# SNAC_7ch_SNES_in_Housing_-_Minimal_with_.net
KiCad netlist of a schematic drawn in EAGLE
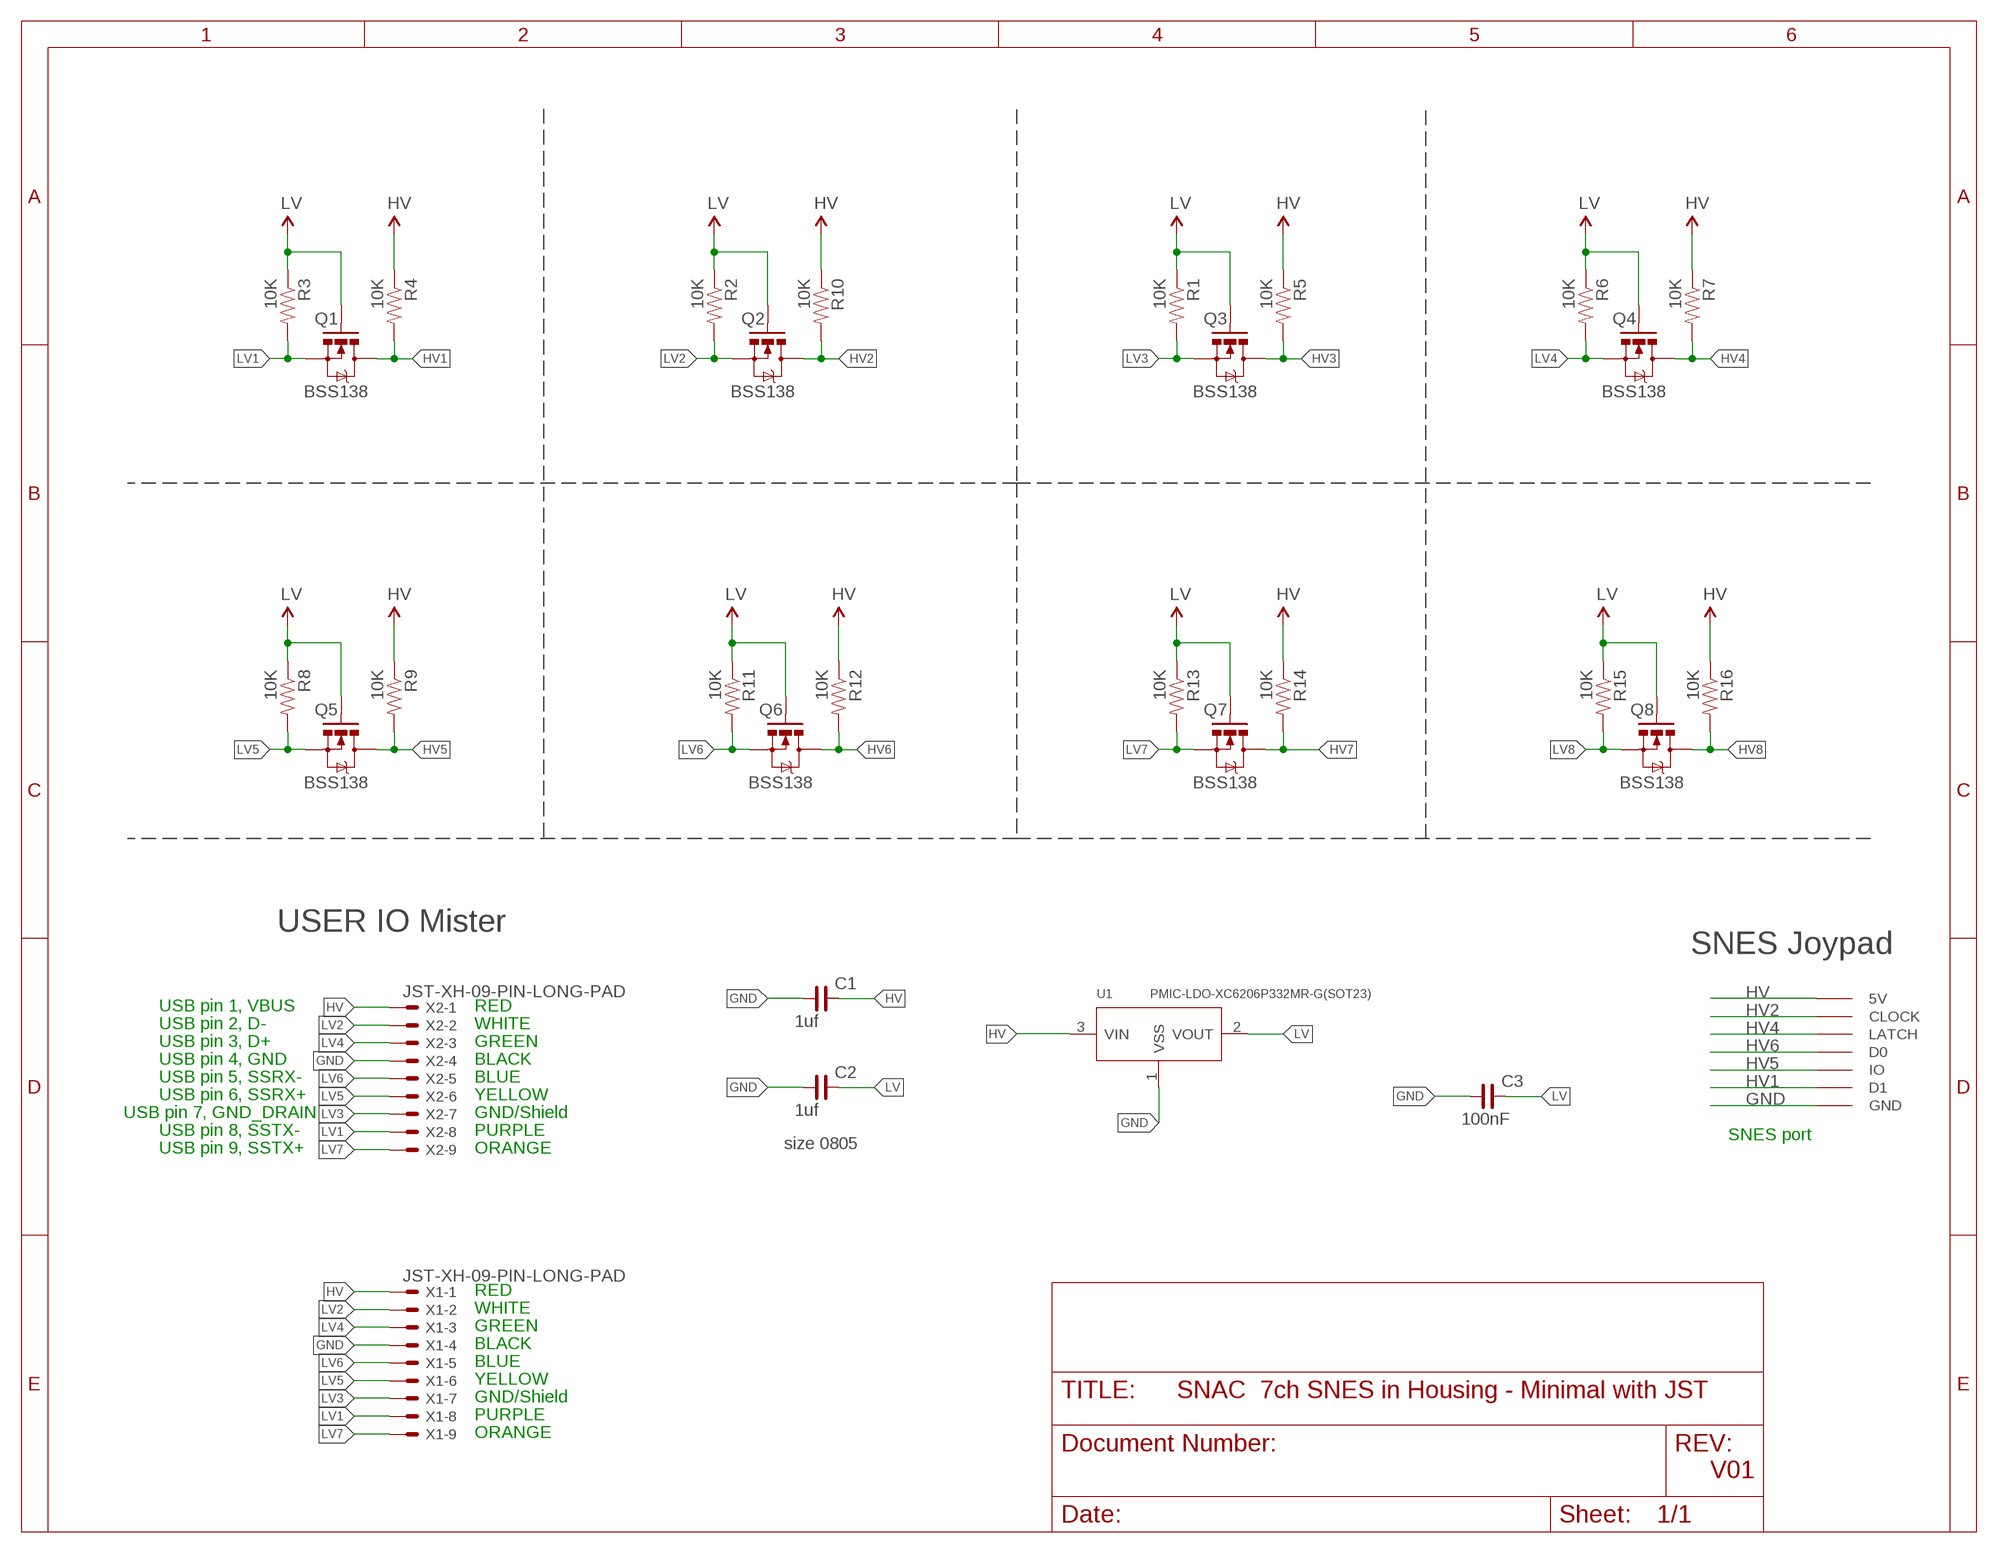
[diagram p0: schematic, sheet 1]

(export (version "E")
  (design (tool "Eeschema 10.0.6"))
  (components
    (comp (ref "C1")
      (value "1uf")
      (footprint "eagle-import:C0805")
      (libsource (lib "eagle-import") (part "C_0805"))
    )
    (comp (ref "C2")
      (value "1uf")
      (footprint "eagle-import:C0805")
      (libsource (lib "eagle-import") (part "C_0805"))
    )
    (comp (ref "C3")
      (value "100nF")
      (footprint "eagle-import:C0805")
      (libsource (lib "eagle-import") (part "C_0805"))
    )
    (comp (ref "Q1")
      (value "BSS138")
      (footprint "eagle-import:SOT23-3")
      (libsource (lib "eagle-import") (part "MOSFET-NCHANNELSMD"))
    )
    (comp (ref "Q2")
      (value "BSS138")
      (footprint "eagle-import:SOT23-3")
      (libsource (lib "eagle-import") (part "MOSFET-NCHANNELSMD"))
    )
    (comp (ref "Q3")
      (value "BSS138")
      (footprint "eagle-import:SOT23-3")
      (libsource (lib "eagle-import") (part "MOSFET-NCHANNELSMD"))
    )
    (comp (ref "Q4")
      (value "BSS138")
      (footprint "eagle-import:SOT23-3")
      (libsource (lib "eagle-import") (part "MOSFET-NCHANNELSMD"))
    )
    (comp (ref "Q5")
      (value "BSS138")
      (footprint "eagle-import:SOT23-3")
      (libsource (lib "eagle-import") (part "MOSFET-NCHANNELSMD"))
    )
    (comp (ref "Q6")
      (value "BSS138")
      (footprint "eagle-import:SOT23-3")
      (libsource (lib "eagle-import") (part "MOSFET-NCHANNELSMD"))
    )
    (comp (ref "Q7")
      (value "BSS138")
      (footprint "eagle-import:SOT23-3")
      (libsource (lib "eagle-import") (part "MOSFET-NCHANNELSMD"))
    )
    (comp (ref "Q8")
      (value "BSS138")
      (footprint "eagle-import:SOT23-3")
      (libsource (lib "eagle-import") (part "MOSFET-NCHANNELSMD"))
    )
    (comp (ref "R1")
      (value "10K")
      (footprint "eagle-import:0603-RES")
      (libsource (lib "eagle-import") (part "RESISTOR0603-RES"))
    )
    (comp (ref "R2")
      (value "10K")
      (footprint "eagle-import:0603-RES")
      (libsource (lib "eagle-import") (part "RESISTOR0603-RES"))
    )
    (comp (ref "R3")
      (value "10K")
      (footprint "eagle-import:0603-RES")
      (libsource (lib "eagle-import") (part "RESISTOR0603-RES"))
    )
    (comp (ref "R4")
      (value "10K")
      (footprint "eagle-import:0603-RES")
      (libsource (lib "eagle-import") (part "RESISTOR0603-RES"))
    )
    (comp (ref "R5")
      (value "10K")
      (footprint "eagle-import:0603-RES")
      (libsource (lib "eagle-import") (part "RESISTOR0603-RES"))
    )
    (comp (ref "R6")
      (value "10K")
      (footprint "eagle-import:0603-RES")
      (libsource (lib "eagle-import") (part "RESISTOR0603-RES"))
    )
    (comp (ref "R7")
      (value "10K")
      (footprint "eagle-import:0603-RES")
      (libsource (lib "eagle-import") (part "RESISTOR0603-RES"))
    )
    (comp (ref "R8")
      (value "10K")
      (footprint "eagle-import:0603-RES")
      (libsource (lib "eagle-import") (part "RESISTOR0603-RES"))
    )
    (comp (ref "R9")
      (value "10K")
      (footprint "eagle-import:0603-RES")
      (libsource (lib "eagle-import") (part "RESISTOR0603-RES"))
    )
    (comp (ref "R10")
      (value "10K")
      (footprint "eagle-import:0603-RES")
      (libsource (lib "eagle-import") (part "RESISTOR0603-RES"))
    )
    (comp (ref "R11")
      (value "10K")
      (footprint "eagle-import:0603-RES")
      (libsource (lib "eagle-import") (part "RESISTOR0603-RES"))
    )
    (comp (ref "R12")
      (value "10K")
      (footprint "eagle-import:0603-RES")
      (libsource (lib "eagle-import") (part "RESISTOR0603-RES"))
    )
    (comp (ref "R13")
      (value "10K")
      (footprint "eagle-import:0603-RES")
      (libsource (lib "eagle-import") (part "RESISTOR0603-RES"))
    )
    (comp (ref "R14")
      (value "10K")
      (footprint "eagle-import:0603-RES")
      (libsource (lib "eagle-import") (part "RESISTOR0603-RES"))
    )
    (comp (ref "R15")
      (value "10K")
      (footprint "eagle-import:0603-RES")
      (libsource (lib "eagle-import") (part "RESISTOR0603-RES"))
    )
    (comp (ref "R16")
      (value "10K")
      (footprint "eagle-import:0603-RES")
      (libsource (lib "eagle-import") (part "RESISTOR0603-RES"))
    )
    (comp (ref "SNES_CON")
      (value "SNESCONN")
      (footprint "eagle-import:SNESCONN")
      (libsource (lib "eagle-import") (part "SNESCONN"))
    )
    (comp (ref "U1")
      (value "PMIC-LDO-XC6206P332MR-G(SOT23)")
      (footprint "eagle-import:SOT-23")
      (fields (field (name "MF") "Torex") (field (name "MP") "XC6206P332MR-G"))
      (libsource (lib "eagle-import") (part "PMIC-LDO-XC6206P332MR-G(SOT23)"))
    )
    (comp (ref "X1")
      (value "JST-XH-09-PIN-LONG-PAD")
      (footprint "eagle-import:JST-XH-09-PACKAGE-LONG-PAD")
      (libsource (lib "eagle-import") (part "JST-XH-09-PIN-LONG-PAD"))
    )
    (comp (ref "X2")
      (value "JST-XH-09-PIN-LONG-PAD")
      (footprint "eagle-import:JST-XH-09-PACKAGE-LONG-PAD")
      (libsource (lib "eagle-import") (part "JST-XH-09-PIN-LONG-PAD"))
    )
  )
  (nets
    (net (code "1") (name "GND") (class "Default")
      (node (ref "C1") (pin "1") (pinfunction "1_1") (pintype "passive"))
      (node (ref "C2") (pin "1") (pinfunction "1_1") (pintype "passive"))
      (node (ref "C3") (pin "1") (pinfunction "1_1") (pintype "passive"))
      (node (ref "SNES_CON") (pin "GND") (pinfunction "GND_GND") (pintype "power_in"))
      (node (ref "U1") (pin "1") (pinfunction "VSS_1") (pintype "power_in"))
      (node (ref "X1") (pin "4") (pinfunction "S_4") (pintype "passive"))
      (node (ref "X2") (pin "4") (pinfunction "S_4") (pintype "passive"))
    )
    (net (code "2") (name "HV") (class "Default")
      (node (ref "C1") (pin "2") (pinfunction "2_2") (pintype "passive"))
      (node (ref "R10") (pin "1") (pinfunction "1_1") (pintype "passive"))
      (node (ref "R12") (pin "1") (pinfunction "1_1") (pintype "passive"))
      (node (ref "R14") (pin "1") (pinfunction "1_1") (pintype "passive"))
      (node (ref "R16") (pin "1") (pinfunction "1_1") (pintype "passive"))
      (node (ref "R4") (pin "1") (pinfunction "1_1") (pintype "passive"))
      (node (ref "R5") (pin "1") (pinfunction "1_1") (pintype "passive"))
      (node (ref "R7") (pin "1") (pinfunction "1_1") (pintype "passive"))
      (node (ref "R9") (pin "1") (pinfunction "1_1") (pintype "passive"))
      (node (ref "SNES_CON") (pin "5V") (pinfunction "5V_5V") (pintype "input"))
      (node (ref "U1") (pin "3") (pinfunction "VIN_3") (pintype "input"))
      (node (ref "X1") (pin "1") (pinfunction "S_1") (pintype "passive"))
      (node (ref "X2") (pin "1") (pinfunction "S_1") (pintype "passive"))
    )
    (net (code "3") (name "HV1") (class "Default")
      (node (ref "Q1") (pin "3") (pinfunction "D_3") (pintype "passive"))
      (node (ref "R4") (pin "2") (pinfunction "2_2") (pintype "passive"))
      (node (ref "SNES_CON") (pin "D1") (pinfunction "D1_D1") (pintype "bidirectional"))
    )
    (net (code "4") (name "HV2") (class "Default")
      (node (ref "Q2") (pin "3") (pinfunction "D_3") (pintype "passive"))
      (node (ref "R10") (pin "2") (pinfunction "2_2") (pintype "passive"))
      (node (ref "SNES_CON") (pin "CLOCK") (pinfunction "CLOCK_CLOCK") (pintype "input"))
    )
    (net (code "5") (name "HV3") (class "Default")
      (node (ref "Q3") (pin "3") (pinfunction "D_3") (pintype "passive"))
      (node (ref "R5") (pin "2") (pinfunction "2_2") (pintype "passive"))
    )
    (net (code "6") (name "HV4") (class "Default")
      (node (ref "Q4") (pin "3") (pinfunction "D_3") (pintype "passive"))
      (node (ref "R7") (pin "2") (pinfunction "2_2") (pintype "passive"))
      (node (ref "SNES_CON") (pin "LATCH") (pinfunction "LATCH_LATCH") (pintype "input"))
    )
    (net (code "7") (name "HV5") (class "Default")
      (node (ref "Q5") (pin "3") (pinfunction "D_3") (pintype "passive"))
      (node (ref "R9") (pin "2") (pinfunction "2_2") (pintype "passive"))
      (node (ref "SNES_CON") (pin "IO") (pinfunction "IO_IO") (pintype "bidirectional"))
    )
    (net (code "8") (name "HV6") (class "Default")
      (node (ref "Q6") (pin "3") (pinfunction "D_3") (pintype "passive"))
      (node (ref "R12") (pin "2") (pinfunction "2_2") (pintype "passive"))
      (node (ref "SNES_CON") (pin "D0") (pinfunction "D0_D0") (pintype "bidirectional"))
    )
    (net (code "9") (name "HV7") (class "Default")
      (node (ref "Q7") (pin "3") (pinfunction "D_3") (pintype "passive"))
      (node (ref "R14") (pin "2") (pinfunction "2_2") (pintype "passive"))
    )
    (net (code "10") (name "HV8") (class "Default")
      (node (ref "Q8") (pin "3") (pinfunction "D_3") (pintype "passive"))
      (node (ref "R16") (pin "2") (pinfunction "2_2") (pintype "passive"))
    )
    (net (code "11") (name "LV") (class "Default")
      (node (ref "C2") (pin "2") (pinfunction "2_2") (pintype "passive"))
      (node (ref "C3") (pin "2") (pinfunction "2_2") (pintype "passive"))
      (node (ref "Q1") (pin "1") (pinfunction "G_1") (pintype "passive"))
      (node (ref "Q2") (pin "1") (pinfunction "G_1") (pintype "passive"))
      (node (ref "Q3") (pin "1") (pinfunction "G_1") (pintype "passive"))
      (node (ref "Q4") (pin "1") (pinfunction "G_1") (pintype "passive"))
      (node (ref "Q5") (pin "1") (pinfunction "G_1") (pintype "passive"))
      (node (ref "Q6") (pin "1") (pinfunction "G_1") (pintype "passive"))
      (node (ref "Q7") (pin "1") (pinfunction "G_1") (pintype "passive"))
      (node (ref "Q8") (pin "1") (pinfunction "G_1") (pintype "passive"))
      (node (ref "R1") (pin "1") (pinfunction "1_1") (pintype "passive"))
      (node (ref "R11") (pin "1") (pinfunction "1_1") (pintype "passive"))
      (node (ref "R13") (pin "1") (pinfunction "1_1") (pintype "passive"))
      (node (ref "R15") (pin "1") (pinfunction "1_1") (pintype "passive"))
      (node (ref "R2") (pin "1") (pinfunction "1_1") (pintype "passive"))
      (node (ref "R3") (pin "1") (pinfunction "1_1") (pintype "passive"))
      (node (ref "R6") (pin "1") (pinfunction "1_1") (pintype "passive"))
      (node (ref "R8") (pin "1") (pinfunction "1_1") (pintype "passive"))
      (node (ref "U1") (pin "2") (pinfunction "VOUT_2") (pintype "output"))
    )
    (net (code "12") (name "LV1") (class "Default")
      (node (ref "Q1") (pin "2") (pinfunction "S_2") (pintype "passive"))
      (node (ref "R3") (pin "2") (pinfunction "2_2") (pintype "passive"))
      (node (ref "X1") (pin "8") (pinfunction "S_8") (pintype "passive"))
      (node (ref "X2") (pin "8") (pinfunction "S_8") (pintype "passive"))
    )
    (net (code "13") (name "LV2") (class "Default")
      (node (ref "Q2") (pin "2") (pinfunction "S_2") (pintype "passive"))
      (node (ref "R2") (pin "2") (pinfunction "2_2") (pintype "passive"))
      (node (ref "X1") (pin "2") (pinfunction "S_2") (pintype "passive"))
      (node (ref "X2") (pin "2") (pinfunction "S_2") (pintype "passive"))
    )
    (net (code "14") (name "LV3") (class "Default")
      (node (ref "Q3") (pin "2") (pinfunction "S_2") (pintype "passive"))
      (node (ref "R1") (pin "2") (pinfunction "2_2") (pintype "passive"))
      (node (ref "X1") (pin "7") (pinfunction "S_7") (pintype "passive"))
      (node (ref "X2") (pin "7") (pinfunction "S_7") (pintype "passive"))
    )
    (net (code "15") (name "LV4") (class "Default")
      (node (ref "Q4") (pin "2") (pinfunction "S_2") (pintype "passive"))
      (node (ref "R6") (pin "2") (pinfunction "2_2") (pintype "passive"))
      (node (ref "X1") (pin "3") (pinfunction "S_3") (pintype "passive"))
      (node (ref "X2") (pin "3") (pinfunction "S_3") (pintype "passive"))
    )
    (net (code "16") (name "LV5") (class "Default")
      (node (ref "Q5") (pin "2") (pinfunction "S_2") (pintype "passive"))
      (node (ref "R8") (pin "2") (pinfunction "2_2") (pintype "passive"))
      (node (ref "X1") (pin "6") (pinfunction "S_6") (pintype "passive"))
      (node (ref "X2") (pin "6") (pinfunction "S_6") (pintype "passive"))
    )
    (net (code "17") (name "LV6") (class "Default")
      (node (ref "Q6") (pin "2") (pinfunction "S_2") (pintype "passive"))
      (node (ref "R11") (pin "2") (pinfunction "2_2") (pintype "passive"))
      (node (ref "X1") (pin "5") (pinfunction "S_5") (pintype "passive"))
      (node (ref "X2") (pin "5") (pinfunction "S_5") (pintype "passive"))
    )
    (net (code "18") (name "LV7") (class "Default")
      (node (ref "Q7") (pin "2") (pinfunction "S_2") (pintype "passive"))
      (node (ref "R13") (pin "2") (pinfunction "2_2") (pintype "passive"))
      (node (ref "X1") (pin "9") (pinfunction "S_9") (pintype "passive"))
      (node (ref "X2") (pin "9") (pinfunction "S_9") (pintype "passive"))
    )
    (net (code "19") (name "LV8") (class "Default")
      (node (ref "Q8") (pin "2") (pinfunction "S_2") (pintype "passive"))
      (node (ref "R15") (pin "2") (pinfunction "2_2") (pintype "passive"))
    )
  )
)
